# scoreboard.net
KiCad netlist of a schematic drawn in EAGLE
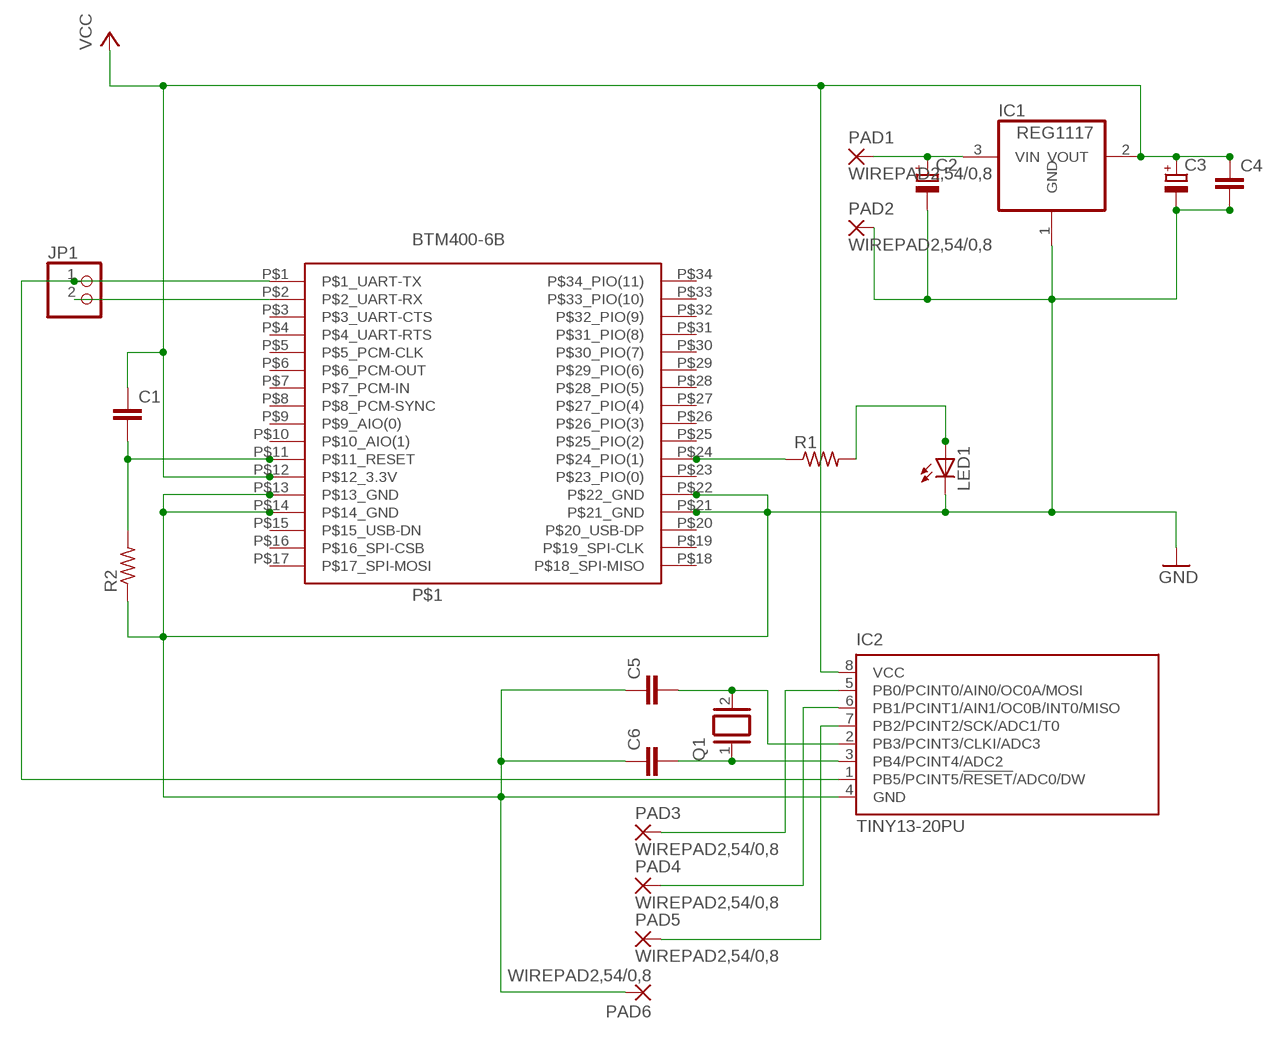
[diagram p0: schematic, sheet 1]

(export (version "E")
  (design (tool "Eeschema 10.0.6"))
  (components
    (comp (ref "C1")
      (value "C-EU025-025X050")
      (footprint "eagle-import:C025-025X050")
      (libsource (lib "eagle-import") (part "C-EU025-025X050"))
    )
    (comp (ref "C2")
      (value "CPOL-EUE2.5-5")
      (footprint "eagle-import:E2,5-5")
      (libsource (lib "eagle-import") (part "CPOL-EUE2.5-5"))
    )
    (comp (ref "C3")
      (value "CPOL-EUE2.5-5")
      (footprint "eagle-import:E2,5-5")
      (libsource (lib "eagle-import") (part "CPOL-EUE2.5-5"))
    )
    (comp (ref "C4")
      (value "C-EU025-025X050")
      (footprint "eagle-import:C025-025X050")
      (libsource (lib "eagle-import") (part "C-EU025-025X050"))
    )
    (comp (ref "C5")
      (value "C-EU025-025X050")
      (footprint "eagle-import:C025-025X050")
      (libsource (lib "eagle-import") (part "C-EU025-025X050"))
    )
    (comp (ref "C6")
      (value "C-EU025-025X050")
      (footprint "eagle-import:C025-025X050")
      (libsource (lib "eagle-import") (part "C-EU025-025X050"))
    )
    (comp (ref "IC1")
      (value "REG1117")
      (footprint "eagle-import:SOT223")
      (libsource (lib "eagle-import") (part "REG1117"))
    )
    (comp (ref "IC2")
      (value "TINY13-20PU")
      (footprint "eagle-import:DIL08")
      (fields (field (name "MPN") "ATTINY13-20PU"))
      (libsource (lib "eagle-import") (part "TINY13PU-20"))
    )
    (comp (ref "JP1")
      (value "PINHD-1X2")
      (footprint "eagle-import:1X02")
      (libsource (lib "eagle-import") (part "PINHD-1X2"))
    )
    (comp (ref "LED1")
      (value "LED5MM")
      (footprint "eagle-import:LED5MM")
      (libsource (lib "eagle-import") (part "LED5MM"))
    )
    (comp (ref "P$1")
      (value "BTM400-6B")
      (footprint "eagle-import:BTM400")
      (libsource (lib "eagle-import") (part "BTM400-6B"))
    )
    (comp (ref "PAD1")
      (value "WIREPAD2,54/0,8")
      (footprint "eagle-import:2,54_0,8")
      (libsource (lib "eagle-import") (part "WIREPAD2,54/0,8"))
    )
    (comp (ref "PAD2")
      (value "WIREPAD2,54/0,8")
      (footprint "eagle-import:2,54_0,8")
      (libsource (lib "eagle-import") (part "WIREPAD2,54/0,8"))
    )
    (comp (ref "PAD3")
      (value "WIREPAD2,54/0,8")
      (footprint "eagle-import:2,54_0,8")
      (libsource (lib "eagle-import") (part "WIREPAD2,54/0,8"))
    )
    (comp (ref "PAD4")
      (value "WIREPAD2,54/0,8")
      (footprint "eagle-import:2,54_0,8")
      (libsource (lib "eagle-import") (part "WIREPAD2,54/0,8"))
    )
    (comp (ref "PAD5")
      (value "WIREPAD2,54/0,8")
      (footprint "eagle-import:2,54_0,8")
      (libsource (lib "eagle-import") (part "WIREPAD2,54/0,8"))
    )
    (comp (ref "PAD6")
      (value "WIREPAD2,54/0,8")
      (footprint "eagle-import:2,54_0,8")
      (libsource (lib "eagle-import") (part "WIREPAD2,54/0,8"))
    )
    (comp (ref "Q1")
      (value "XTAL/S")
      (footprint "eagle-import:QS")
      (libsource (lib "eagle-import") (part "XTAL/S"))
    )
    (comp (ref "R1")
      (value "R-US_0207/10")
      (footprint "eagle-import:0207_10")
      (libsource (lib "eagle-import") (part "R-US_0207/10"))
    )
    (comp (ref "R2")
      (value "R-US_0207/10")
      (footprint "eagle-import:0207_10")
      (libsource (lib "eagle-import") (part "R-US_0207/10"))
    )
  )
  (nets
    (net (code "1") (name "GND") (class "Default")
      (node (ref "C2") (pin "-") (pinfunction "-_-") (pintype "passive"))
      (node (ref "C3") (pin "-") (pinfunction "-_-") (pintype "passive"))
      (node (ref "C4") (pin "2") (pinfunction "2_2") (pintype "passive"))
      (node (ref "C5") (pin "1") (pinfunction "1_1") (pintype "passive"))
      (node (ref "C6") (pin "1") (pinfunction "1_1") (pintype "passive"))
      (node (ref "IC1") (pin "1") (pinfunction "GND_1") (pintype "power_in"))
      (node (ref "IC2") (pin "4") (pinfunction "GND_4") (pintype "power_in"))
      (node (ref "LED1") (pin "K") (pinfunction "C_K") (pintype "passive"))
      (node (ref "P$1") (pin "P$13") (pinfunction "P$13_GND_P$13") (pintype "power_in"))
      (node (ref "P$1") (pin "P$14") (pinfunction "P$14_GND_P$14") (pintype "power_in"))
      (node (ref "P$1") (pin "P$21") (pinfunction "P$21_GND_P$21") (pintype "power_in"))
      (node (ref "P$1") (pin "P$22") (pinfunction "P$22_GND_P$22") (pintype "power_in"))
      (node (ref "PAD2") (pin "1") (pinfunction "P_1") (pintype "passive"))
      (node (ref "PAD6") (pin "1") (pinfunction "P_1") (pintype "passive"))
      (node (ref "R2") (pin "1") (pinfunction "1_1") (pintype "passive"))
    )
    (net (code "2") (name "Net-(IC1-VIN)") (class "Default")
      (node (ref "C2") (pin "+") (pinfunction "+_+") (pintype "passive"))
      (node (ref "IC1") (pin "3") (pinfunction "VIN_3") (pintype "input"))
      (node (ref "PAD1") (pin "1") (pinfunction "P_1") (pintype "passive"))
    )
    (net (code "3") (name "Net-(IC2-PB0{slash}PCINT0{slash}AIN0{slash}OC0A{slash}MOSI)") (class "Default")
      (node (ref "IC2") (pin "5") (pinfunction "PB0/PCINT0/AIN0/OC0A/MOSI_5") (pintype "bidirectional"))
      (node (ref "PAD3") (pin "1") (pinfunction "P_1") (pintype "passive"))
    )
    (net (code "4") (name "Net-(IC2-PB1{slash}PCINT1{slash}AIN1{slash}OC0B{slash}INT0{slash}MISO)") (class "Default")
      (node (ref "IC2") (pin "6") (pinfunction "PB1/PCINT1/AIN1/OC0B/INT0/MISO_6") (pintype "bidirectional"))
      (node (ref "PAD4") (pin "1") (pinfunction "P_1") (pintype "passive"))
    )
    (net (code "5") (name "Net-(IC2-PB2{slash}PCINT2{slash}SCK{slash}ADC1{slash}T0)") (class "Default")
      (node (ref "IC2") (pin "7") (pinfunction "PB2/PCINT2/SCK/ADC1/T0_7") (pintype "bidirectional"))
      (node (ref "PAD5") (pin "1") (pinfunction "P_1") (pintype "passive"))
    )
    (net (code "6") (name "Net-(IC2-PB3{slash}PCINT3{slash}CLKI{slash}ADC3)") (class "Default")
      (node (ref "C5") (pin "2") (pinfunction "2_2") (pintype "passive"))
      (node (ref "IC2") (pin "2") (pinfunction "PB3/PCINT3/CLKI/ADC3_2") (pintype "bidirectional"))
      (node (ref "Q1") (pin "2") (pinfunction "2_2") (pintype "passive"))
    )
    (net (code "7") (name "Net-(IC2-PB4{slash}PCINT4{slash}ADC2)") (class "Default")
      (node (ref "C6") (pin "2") (pinfunction "2_2") (pintype "passive"))
      (node (ref "IC2") (pin "3") (pinfunction "PB4/PCINT4/ADC2_3") (pintype "bidirectional"))
      (node (ref "Q1") (pin "1") (pinfunction "1_1") (pintype "passive"))
    )
    (net (code "8") (name "Net-(IC2-PB5{slash}PCINT5{slash}~{RESET}{slash}ADC0{slash}DW)") (class "Default")
      (node (ref "IC2") (pin "1") (pinfunction "PB5/PCINT5/~{RESET}/ADC0/DW_1") (pintype "bidirectional"))
      (node (ref "JP1") (pin "1") (pinfunction "1_1") (pintype "passive"))
      (node (ref "P$1") (pin "P$1") (pinfunction "P$1_UART-TX_P$1") (pintype "output"))
    )
    (net (code "9") (name "Net-(LED1-PadA)") (class "Default")
      (node (ref "LED1") (pin "A") (pinfunction "A_A") (pintype "passive"))
      (node (ref "R1") (pin "2") (pinfunction "2_2") (pintype "passive"))
    )
    (net (code "10") (name "Net-(P$1-P$2_UART-RX)") (class "Default")
      (node (ref "JP1") (pin "2") (pinfunction "2_2") (pintype "passive"))
      (node (ref "P$1") (pin "P$2") (pinfunction "P$2_UART-RX_P$2") (pintype "input"))
    )
    (net (code "11") (name "Net-(P$1-P$11_RESET)") (class "Default")
      (node (ref "C1") (pin "2") (pinfunction "2_2") (pintype "passive"))
      (node (ref "P$1") (pin "P$11") (pinfunction "P$11_RESET_P$11") (pintype "input"))
      (node (ref "R2") (pin "2") (pinfunction "2_2") (pintype "passive"))
    )
    (net (code "12") (name "Net-(P$1-P$24_PIO(1))") (class "Default")
      (node (ref "P$1") (pin "P$24") (pinfunction "P$24_PIO(1)_P$24") (pintype "bidirectional"))
      (node (ref "R1") (pin "1") (pinfunction "1_1") (pintype "passive"))
    )
    (net (code "13") (name "VCC") (class "Default")
      (node (ref "C1") (pin "1") (pinfunction "1_1") (pintype "passive"))
      (node (ref "C3") (pin "+") (pinfunction "+_+") (pintype "passive"))
      (node (ref "C4") (pin "1") (pinfunction "1_1") (pintype "passive"))
      (node (ref "IC1") (pin "2") (pinfunction "VOUT_2") (pintype "output"))
      (node (ref "IC2") (pin "8") (pinfunction "VCC_8") (pintype "power_in"))
      (node (ref "P$1") (pin "P$12") (pinfunction "P$12_3.3V_P$12") (pintype "power_in"))
    )
    (net (code "14") (name "unconnected-(P$1-P$3_UART-CTS-PadP$3)") (class "Default")
      (node (ref "P$1") (pin "P$3") (pinfunction "P$3_UART-CTS_P$3") (pintype "input"))
    )
    (net (code "15") (name "unconnected-(P$1-P$4_UART-RTS-PadP$4)") (class "Default")
      (node (ref "P$1") (pin "P$4") (pinfunction "P$4_UART-RTS_P$4") (pintype "output"))
    )
    (net (code "16") (name "unconnected-(P$1-P$5_PCM-CLK-PadP$5)") (class "Default")
      (node (ref "P$1") (pin "P$5") (pinfunction "P$5_PCM-CLK_P$5") (pintype "bidirectional"))
    )
    (net (code "17") (name "unconnected-(P$1-P$6_PCM-OUT-PadP$6)") (class "Default")
      (node (ref "P$1") (pin "P$6") (pinfunction "P$6_PCM-OUT_P$6") (pintype "output"))
    )
    (net (code "18") (name "unconnected-(P$1-P$7_PCM-IN-PadP$7)") (class "Default")
      (node (ref "P$1") (pin "P$7") (pinfunction "P$7_PCM-IN_P$7") (pintype "input"))
    )
    (net (code "19") (name "unconnected-(P$1-P$8_PCM-SYNC-PadP$8)") (class "Default")
      (node (ref "P$1") (pin "P$8") (pinfunction "P$8_PCM-SYNC_P$8") (pintype "bidirectional"))
    )
    (net (code "20") (name "unconnected-(P$1-P$9_AIO(0)-PadP$9)") (class "Default")
      (node (ref "P$1") (pin "P$9") (pinfunction "P$9_AIO(0)_P$9") (pintype "bidirectional"))
    )
    (net (code "21") (name "unconnected-(P$1-P$10_AIO(1)-PadP$10)") (class "Default")
      (node (ref "P$1") (pin "P$10") (pinfunction "P$10_AIO(1)_P$10") (pintype "bidirectional"))
    )
    (net (code "22") (name "unconnected-(P$1-P$15_USB-DN-PadP$15)") (class "Default")
      (node (ref "P$1") (pin "P$15") (pinfunction "P$15_USB-DN_P$15") (pintype "bidirectional"))
    )
    (net (code "23") (name "unconnected-(P$1-P$16_SPI-CSB-PadP$16)") (class "Default")
      (node (ref "P$1") (pin "P$16") (pinfunction "P$16_SPI-CSB_P$16") (pintype "input"))
    )
    (net (code "24") (name "unconnected-(P$1-P$17_SPI-MOSI-PadP$17)") (class "Default")
      (node (ref "P$1") (pin "P$17") (pinfunction "P$17_SPI-MOSI_P$17") (pintype "input"))
    )
    (net (code "25") (name "unconnected-(P$1-P$18_SPI-MISO-PadP$18)") (class "Default")
      (node (ref "P$1") (pin "P$18") (pinfunction "P$18_SPI-MISO_P$18") (pintype "output"))
    )
    (net (code "26") (name "unconnected-(P$1-P$19_SPI-CLK-PadP$19)") (class "Default")
      (node (ref "P$1") (pin "P$19") (pinfunction "P$19_SPI-CLK_P$19") (pintype "input"))
    )
    (net (code "27") (name "unconnected-(P$1-P$20_USB-DP-PadP$20)") (class "Default")
      (node (ref "P$1") (pin "P$20") (pinfunction "P$20_USB-DP_P$20") (pintype "bidirectional"))
    )
    (net (code "28") (name "unconnected-(P$1-P$23_PIO(0)-PadP$23)") (class "Default")
      (node (ref "P$1") (pin "P$23") (pinfunction "P$23_PIO(0)_P$23") (pintype "bidirectional"))
    )
    (net (code "29") (name "unconnected-(P$1-P$25_PIO(2)-PadP$25)") (class "Default")
      (node (ref "P$1") (pin "P$25") (pinfunction "P$25_PIO(2)_P$25") (pintype "bidirectional"))
    )
    (net (code "30") (name "unconnected-(P$1-P$26_PIO(3)-PadP$26)") (class "Default")
      (node (ref "P$1") (pin "P$26") (pinfunction "P$26_PIO(3)_P$26") (pintype "bidirectional"))
    )
    (net (code "31") (name "unconnected-(P$1-P$27_PIO(4)-PadP$27)") (class "Default")
      (node (ref "P$1") (pin "P$27") (pinfunction "P$27_PIO(4)_P$27") (pintype "bidirectional"))
    )
    (net (code "32") (name "unconnected-(P$1-P$28_PIO(5)-PadP$28)") (class "Default")
      (node (ref "P$1") (pin "P$28") (pinfunction "P$28_PIO(5)_P$28") (pintype "bidirectional"))
    )
    (net (code "33") (name "unconnected-(P$1-P$29_PIO(6)-PadP$29)") (class "Default")
      (node (ref "P$1") (pin "P$29") (pinfunction "P$29_PIO(6)_P$29") (pintype "bidirectional"))
    )
    (net (code "34") (name "unconnected-(P$1-P$30_PIO(7)-PadP$30)") (class "Default")
      (node (ref "P$1") (pin "P$30") (pinfunction "P$30_PIO(7)_P$30") (pintype "bidirectional"))
    )
    (net (code "35") (name "unconnected-(P$1-P$31_PIO(8)-PadP$31)") (class "Default")
      (node (ref "P$1") (pin "P$31") (pinfunction "P$31_PIO(8)_P$31") (pintype "bidirectional"))
    )
    (net (code "36") (name "unconnected-(P$1-P$32_PIO(9)-PadP$32)") (class "Default")
      (node (ref "P$1") (pin "P$32") (pinfunction "P$32_PIO(9)_P$32") (pintype "bidirectional"))
    )
    (net (code "37") (name "unconnected-(P$1-P$33_PIO(10)-PadP$33)") (class "Default")
      (node (ref "P$1") (pin "P$33") (pinfunction "P$33_PIO(10)_P$33") (pintype "bidirectional"))
    )
    (net (code "38") (name "unconnected-(P$1-P$34_PIO(11)-PadP$34)") (class "Default")
      (node (ref "P$1") (pin "P$34") (pinfunction "P$34_PIO(11)_P$34") (pintype "bidirectional"))
    )
  )
)
